# Power_Supply.net
KiCad netlist of a schematic drawn in Altium Designer
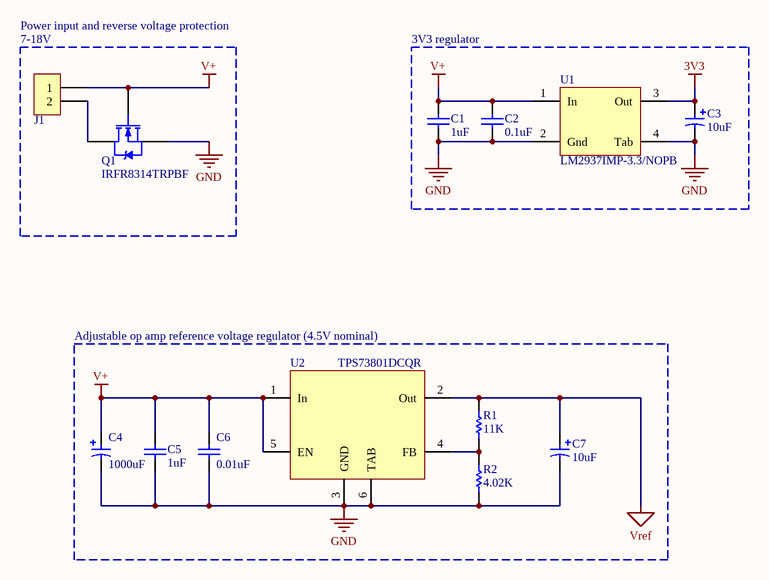
[diagram p0: Power_Supply.SchDoc]

(export (version "E")
  (design (tool "Eeschema 10.0.6"))
  (components
    (comp (ref "C1")
      (value "1uF")
      (footprint "CAPC1608X09N")
      (fields
        (field (name "DIGIKEY PART NUMBER") "490-10487-1-ND")
        (field (name "VOLTAGE") "35V")
        (field (name "MANUFACTURER") "Murata")
      )
      (libsource (lib "Speaker Library") (part "CAP CER 1uF 0603"))
    )
    (comp (ref "C2")
      (value "0.1uF")
      (footprint "CAPC1608X09N")
      (fields
        (field (name "DIGIKEY PART NUMBER") "490-1519-1-ND")
        (field (name "VOLTAGE") "50V")
        (field (name "TOLERANCE") "10%")
      )
      (libsource (lib "Speaker Library") (part "CAP CER 0.1uF 0603"))
    )
    (comp (ref "C3")
      (value "10uF")
      (footprint "CAPMP3216X18N")
      (fields
        (field (name "DIGIKEY PART NUMBER") "399-8431-1-ND")
        (field (name "VOLTAGE") "10V")
        (field (name "TOLERANCE") "10%")
      )
      (libsource (lib "Speaker Library") (part "CAP TANT 10uF 1.8 OHM 10V 1206"))
    )
    (comp (ref "C4")
      (value "1000uF")
      (footprint "Nichicon UVZ 5mm")
      (description "Input Bulk Cap")
      (fields (field (name "DIGIKEY PART NUMBER") "493-1305-ND") (field (name "MANUFACTURER") "Nichicon"))
      (libsource (lib "Speaker Library") (part "CAP ALUM 1000uF SMD"))
    )
    (comp (ref "C5")
      (value "1uF")
      (footprint "CAPC1608X09N")
      (fields
        (field (name "DIGIKEY PART NUMBER") "490-10487-1-ND")
        (field (name "VOLTAGE") "35V")
        (field (name "MANUFACTURER") "Murata")
      )
      (libsource (lib "Speaker Library") (part "CAP CER 1uF 0603"))
    )
    (comp (ref "C6")
      (value "0.01uF")
      (footprint "CAPC1608X09N")
      (fields (field (name "DIGIKEY PART NUMBER") "490-9666-1-ND") (field (name "MANUFACTURER") "Murata"))
      (libsource (lib "Speaker Library") (part "CAP CER 0.01uF 0603"))
    )
    (comp (ref "C7")
      (value "10uF")
      (footprint "CAPMP3216X18N")
      (fields
        (field (name "DIGIKEY PART NUMBER") "399-8431-1-ND")
        (field (name "VOLTAGE") "10V")
        (field (name "TOLERANCE") "10%")
      )
      (libsource (lib "Speaker Library") (part "CAP TANT 10uF 1.8 OHM 10V 1206"))
    )
    (comp (ref "J1")
      (value "TERMINAL BLOCK 2POS")
      (footprint "TERMINAL BLOCK 5MM 2POS")
      (fields (field (name "DIGIKEY PART NUMBER") "ED2561-ND"))
      (libsource (lib "Speaker Library") (part "TERMINAL BLOCK 2POS"))
    )
    (comp (ref "Q1")
      (value "IRFR8314TRPBF")
      (footprint "DPAK229P991X239-3N")
      (description "Reverse Voltage Power MOSFET")
      (fields
        (field (name "DIGIKEY PART NUMBER") "IRFR8314TRPBFCT-ND")
        (field (name "MANUFACTURER") "Infineon Technologies")
      )
      (libsource (lib "Speaker Library") (part "MOSFET_N_CH_30V_179A_D2PAK"))
    )
    (comp (ref "R1")
      (value "11K")
      (footprint "RESC1608X06N")
      (fields
        (field (name "TOLERANCE") "1%")
        (field (name "POWER") "0.1W")
        (field (name "MANUFACTURER") "Yageo")
      )
      (libsource (lib "Speaker Library") (part "RES 11K 0603"))
    )
    (comp (ref "R2")
      (value "4.02K")
      (footprint "RESC1608X06N")
      (fields (field (name "TOLERANCE") "1%") (field (name "DIGIKEY PART NUMBER") "311-4.02KHRCT-ND"))
      (libsource (lib "Speaker Library") (part "RES 4.02K 0603"))
    )
    (comp (ref "U1")
      (value "LM2937IMP-3.3/NOPB")
      (footprint "SOT230P700X180-4N (DCY)")
      (fields (field (name "DIGIKEY PART NUMBER") "LM2937IMP-3.3/NOPBCT-ND"))
      (libsource (lib "Speaker Library") (part "LM2937IMP-3.3/NOPB"))
    )
    (comp (ref "U2")
      (value "TPS73801DCQR")
      (footprint "SOT127P705X180-6M (DCQ)")
      (description "Adjustable 1.21V-20V 1A Regulator")
      (fields (field (name "DIGIKEY PART NUMBER") "296-39489-1-ND"))
      (libsource (lib "Speaker Library") (part "TPS73801DCQR"))
    )
  )
  (nets
    (net (code "1") (name "3V3") (class "Default")
      (node (ref "C3") (pin "1") (pinfunction "1_1") (pintype "passive"))
      (node (ref "U1") (pin "3") (pinfunction "Out_3") (pintype "power_in"))
    )
    (net (code "2") (name "GND") (class "Default")
      (node (ref "C1") (pin "2") (pinfunction "2_2") (pintype "passive"))
      (node (ref "C2") (pin "1") (pinfunction "1_1") (pintype "passive"))
      (node (ref "C3") (pin "2") (pinfunction "2_2") (pintype "passive"))
      (node (ref "C4") (pin "2") (pinfunction "2_2") (pintype "passive"))
      (node (ref "C5") (pin "2") (pinfunction "2_2") (pintype "passive"))
      (node (ref "C6") (pin "1") (pinfunction "1_1") (pintype "passive"))
      (node (ref "C7") (pin "2") (pinfunction "2_2") (pintype "passive"))
      (node (ref "Q1") (pin "3") (pinfunction "S_3") (pintype "passive"))
      (node (ref "R2") (pin "1") (pinfunction "1_1") (pintype "passive"))
      (node (ref "U1") (pin "2") (pinfunction "Gnd_2") (pintype "power_in"))
      (node (ref "U1") (pin "4") (pinfunction "Tab_4") (pintype "power_in"))
      (node (ref "U2") (pin "3") (pinfunction "GND_3") (pintype "power_in"))
      (node (ref "U2") (pin "6") (pinfunction "TAB_6") (pintype "power_in"))
    )
    (net (code "3") (name "Net-(Q1-D)") (class "Default")
      (node (ref "J1") (pin "2") (pinfunction "2_2") (pintype "passive"))
      (node (ref "Q1") (pin "4") (pinfunction "D_4") (pintype "passive"))
    )
    (net (code "4") (name "Net-(U2-FB)") (class "Default")
      (node (ref "R1") (pin "1") (pinfunction "1_1") (pintype "passive"))
      (node (ref "R2") (pin "2") (pinfunction "2_2") (pintype "passive"))
      (node (ref "U2") (pin "4") (pinfunction "FB_4") (pintype "power_in"))
    )
    (net (code "5") (name "V+") (class "Default")
      (node (ref "C1") (pin "1") (pinfunction "1_1") (pintype "passive"))
      (node (ref "C2") (pin "2") (pinfunction "2_2") (pintype "passive"))
      (node (ref "C4") (pin "1") (pinfunction "1_1") (pintype "passive"))
      (node (ref "C5") (pin "1") (pinfunction "1_1") (pintype "passive"))
      (node (ref "C6") (pin "2") (pinfunction "2_2") (pintype "passive"))
      (node (ref "J1") (pin "1") (pinfunction "1_1") (pintype "passive"))
      (node (ref "Q1") (pin "1") (pinfunction "G_1") (pintype "passive"))
      (node (ref "U1") (pin "1") (pinfunction "In_1") (pintype "power_in"))
      (node (ref "U2") (pin "1") (pinfunction "In_1") (pintype "power_in"))
      (node (ref "U2") (pin "5") (pinfunction "EN_5") (pintype "passive"))
    )
    (net (code "6") (name "Vref") (class "Default")
      (node (ref "C7") (pin "1") (pinfunction "1_1") (pintype "passive"))
      (node (ref "R1") (pin "2") (pinfunction "2_2") (pintype "passive"))
      (node (ref "U2") (pin "2") (pinfunction "Out_2") (pintype "power_in"))
    )
  )
)
